# SCH_RTC_SYS_2022-07-16.net
KiCad netlist of a schematic drawn in EasyEDA
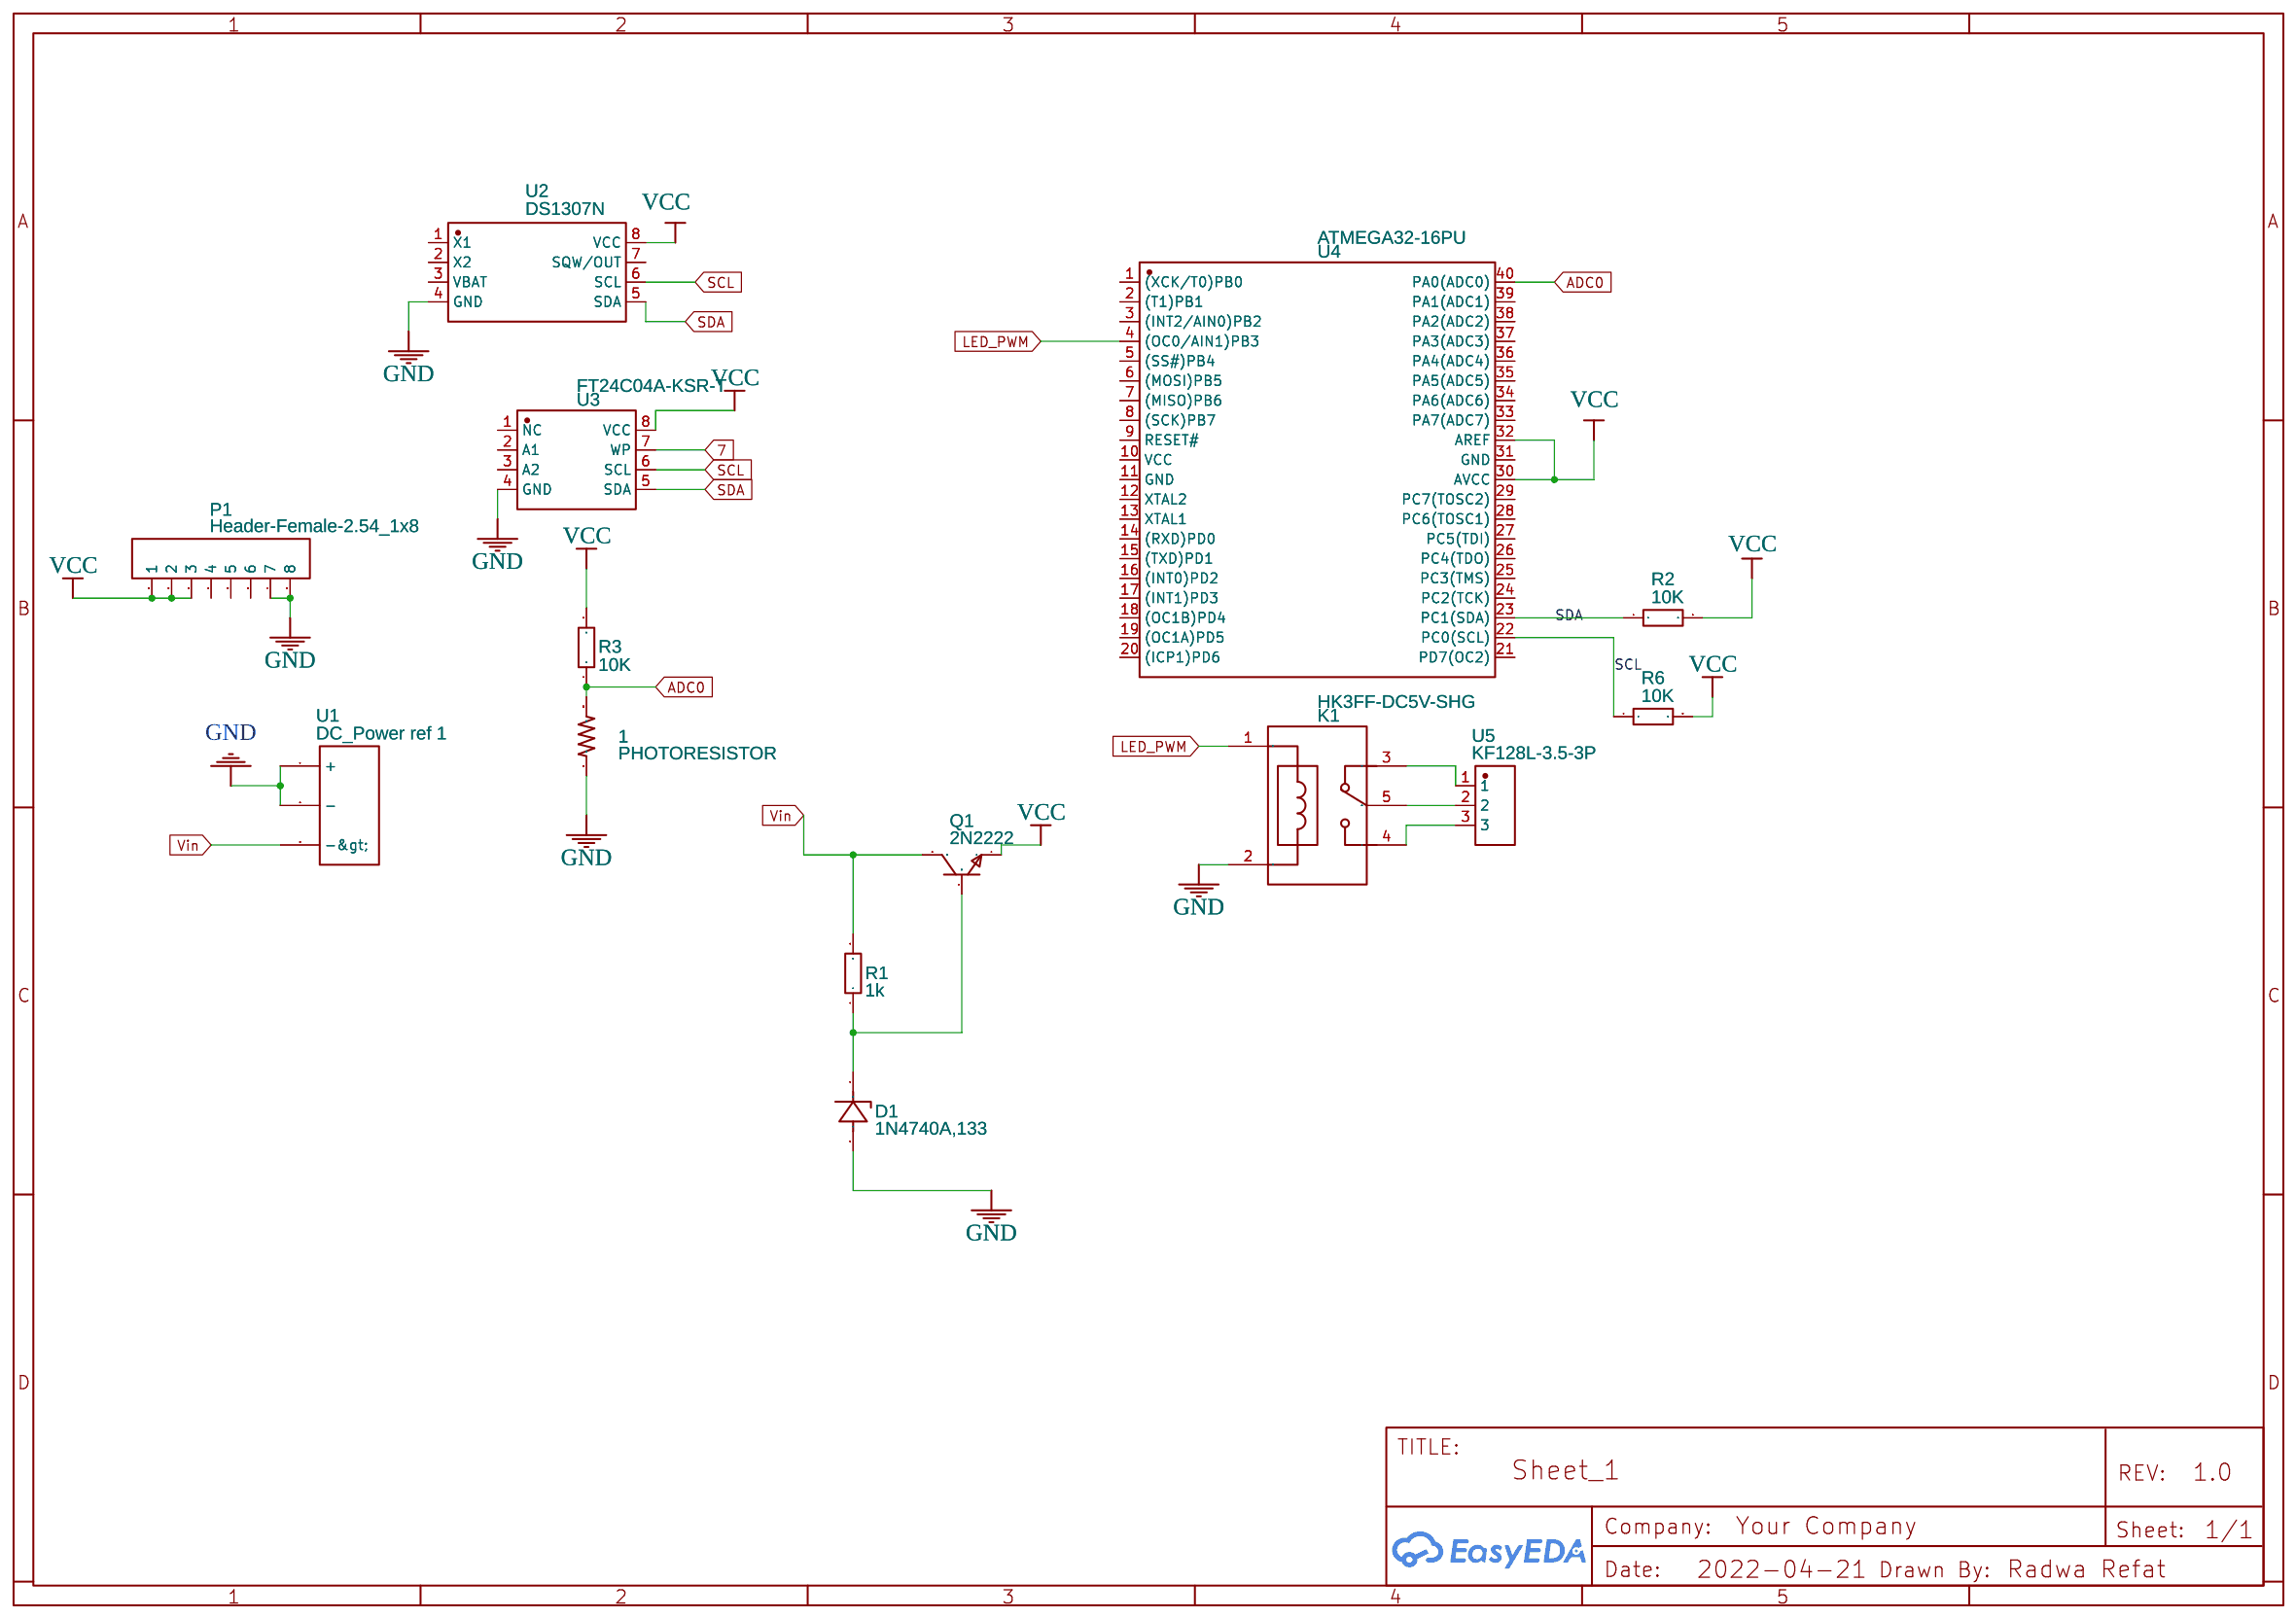
[diagram p0: schematic sheet]

(export (version "E")
  (design (tool "Eeschema 10.0.6"))
  (components
    (comp (ref "1") (value "PHOTORESISTOR") (libsource (lib "") (part "PHOTORESISTOR")))
    (comp (ref "D1")
      (value "1N4740A,133")
      (fields (field (name "BOM_Supplier Part") "C551363"))
      (libsource (lib "") (part "1N4740A,133"))
    )
    (comp (ref "K1")
      (value "HK3FF-DC5V-SHG")
      (fields (field (name "BOM_Supplier Part") "C27840"))
      (libsource (lib "") (part "HK3FF-DC5V-SHG"))
    )
    (comp (ref "P1")
      (value "Header-Female-2.54_1x8")
      (fields
        (field (name "BOM_Manufacturer Part") "Female headerHDR1X8-2.54")
        (field (name "BOM_Supplier Part") "C27438")
      )
      (libsource (lib "") (part "Header-Female-2.54_1x8"))
    )
    (comp (ref "Q1")
      (value "2N2222")
      (fields (field (name "BOM_Supplier Part") "C118536"))
      (libsource (lib "") (part "2N2222"))
    )
    (comp (ref "R1")
      (value "1k")
      (fields (field (name "BOM_Supplier Part") "C337046"))
      (libsource (lib "") (part "MF1/4WS ±1% 10K OTB5"))
    )
    (comp (ref "R2")
      (value "10K")
      (fields (field (name "BOM_Supplier Part") "C337046"))
      (libsource (lib "") (part "MF1/4WS ±1% 10K OTB5_1"))
    )
    (comp (ref "R3")
      (value "10K")
      (fields (field (name "BOM_Supplier Part") "C337046"))
      (libsource (lib "") (part "MF1/4WS ±1% 10K OTB5"))
    )
    (comp (ref "R6")
      (value "10K")
      (fields (field (name "BOM_Supplier Part") "C337046"))
      (libsource (lib "") (part "MF1/4WS ±1% 10K OTB5_1"))
    )
    (comp (ref "U1")
      (value "DC_Power ref 1")
      (fields (field (name "Manufacturer") "Kobiconn") (field (name "BOM_Manufacturer Part") "163-179PH-EX"))
      (libsource (lib "") (part "DC_Power ref 1"))
    )
    (comp (ref "U2")
      (value "DS1307N")
      (fields (field (name "BOM_Supplier Part") "C434596"))
      (libsource (lib "") (part "DS1307N"))
    )
    (comp (ref "U3")
      (value "FT24C04A-KSR-T")
      (fields (field (name "BOM_Supplier Part") "C232866"))
      (libsource (lib "") (part "FT24C04A-KSR-T"))
    )
    (comp (ref "U4")
      (value "ATMEGA32-16PU")
      (fields (field (name "BOM_Supplier Part") "C1337273"))
      (libsource (lib "") (part "ATMEGA32-16PU"))
    )
    (comp (ref "U5")
      (value "KF128L-3.5-3P")
      (fields (field (name "BOM_Supplier Part") "C474931"))
      (libsource (lib "") (part "KF128L-3.5-3P"))
    )
  )
  (nets
    (net (code "1") (name "7") (class "Default")
      (node (ref "U3") (pin "7") (pinfunction "WP_7") (pintype "unspecified"))
    )
    (net (code "2") (name "ADC0") (class "Default")
      (node (ref "1") (pin "P$2") (pinfunction "2_P$2") (pintype "bidirectional"))
      (node (ref "R3") (pin "1") (pinfunction "1_1") (pintype "input"))
      (node (ref "U4") (pin "40") (pinfunction "PA0(ADC0)_40") (pintype "unspecified"))
    )
    (net (code "3") (name "GND") (class "Default")
      (node (ref "1") (pin "P$1") (pinfunction "1_P$1") (pintype "bidirectional"))
      (node (ref "D1") (pin "2") (pinfunction "A_2") (pintype "unspecified"))
      (node (ref "K1") (pin "2") (pinfunction "2_2") (pintype "unspecified"))
      (node (ref "P1") (pin "7") (pinfunction "7_7") (pintype "input"))
      (node (ref "P1") (pin "8") (pinfunction "8_8") (pintype "input"))
      (node (ref "U1") (pin "1") (pinfunction "+_1") (pintype "unspecified"))
      (node (ref "U1") (pin "2") (pinfunction "-_2") (pintype "unspecified"))
      (node (ref "U2") (pin "4") (pinfunction "GND_4") (pintype "unspecified"))
      (node (ref "U3") (pin "4") (pinfunction "GND_4") (pintype "unspecified"))
    )
    (net (code "4") (name "LED_PWM") (class "Default")
      (node (ref "K1") (pin "1") (pinfunction "1_1") (pintype "unspecified"))
      (node (ref "U4") (pin "4") (pinfunction "(OC0/AIN1)PB3_4") (pintype "unspecified"))
    )
    (net (code "5") (name "Net-(D1-K)") (class "Default")
      (node (ref "D1") (pin "1") (pinfunction "K_1") (pintype "unspecified"))
      (node (ref "Q1") (pin "2") (pinfunction "B_2") (pintype "unspecified"))
      (node (ref "R1") (pin "1") (pinfunction "1_1") (pintype "input"))
    )
    (net (code "6") (name "Net-(K1-Pad3)") (class "Default")
      (node (ref "K1") (pin "3") (pinfunction "3_3") (pintype "unspecified"))
      (node (ref "U5") (pin "1") (pinfunction "1_1") (pintype "unspecified"))
    )
    (net (code "7") (name "Net-(K1-Pad4)") (class "Default")
      (node (ref "K1") (pin "4") (pinfunction "4_4") (pintype "unspecified"))
      (node (ref "U5") (pin "3") (pinfunction "3_3") (pintype "unspecified"))
    )
    (net (code "8") (name "Net-(K1-Pad5)") (class "Default")
      (node (ref "K1") (pin "5") (pinfunction "5_5") (pintype "unspecified"))
      (node (ref "U5") (pin "2") (pinfunction "2_2") (pintype "unspecified"))
    )
    (net (code "9") (name "SCL") (class "Default")
      (node (ref "R6") (pin "1") (pinfunction "1_1") (pintype "input"))
      (node (ref "U2") (pin "6") (pinfunction "SCL_6") (pintype "unspecified"))
      (node (ref "U3") (pin "6") (pinfunction "SCL_6") (pintype "unspecified"))
      (node (ref "U4") (pin "22") (pinfunction "PC0(SCL)_22") (pintype "unspecified"))
    )
    (net (code "10") (name "SDA") (class "Default")
      (node (ref "R2") (pin "1") (pinfunction "1_1") (pintype "input"))
      (node (ref "U2") (pin "5") (pinfunction "SDA_5") (pintype "unspecified"))
      (node (ref "U3") (pin "5") (pinfunction "SDA_5") (pintype "unspecified"))
      (node (ref "U4") (pin "23") (pinfunction "PC1(SDA)_23") (pintype "unspecified"))
    )
    (net (code "11") (name "VCC") (class "Default")
      (node (ref "P1") (pin "1") (pinfunction "1_1") (pintype "input"))
      (node (ref "P1") (pin "2") (pinfunction "2_2") (pintype "input"))
      (node (ref "P1") (pin "3") (pinfunction "3_3") (pintype "input"))
      (node (ref "Q1") (pin "1") (pinfunction "E_1") (pintype "unspecified"))
      (node (ref "R2") (pin "2") (pinfunction "2_2") (pintype "input"))
      (node (ref "R3") (pin "2") (pinfunction "2_2") (pintype "input"))
      (node (ref "R6") (pin "2") (pinfunction "2_2") (pintype "input"))
      (node (ref "U2") (pin "8") (pinfunction "VCC_8") (pintype "unspecified"))
      (node (ref "U3") (pin "8") (pinfunction "VCC_8") (pintype "unspecified"))
      (node (ref "U4") (pin "30") (pinfunction "AVCC_30") (pintype "unspecified"))
      (node (ref "U4") (pin "32") (pinfunction "AREF_32") (pintype "unspecified"))
    )
    (net (code "12") (name "Vin") (class "Default")
      (node (ref "Q1") (pin "3") (pinfunction "C_3") (pintype "unspecified"))
      (node (ref "R1") (pin "2") (pinfunction "2_2") (pintype "input"))
      (node (ref "U1") (pin "3") (pinfunction "-&gt;_3") (pintype "unspecified"))
    )
    (net (code "13") (name "unconnected-(P1-Pad4)") (class "Default")
      (node (ref "P1") (pin "4") (pinfunction "4_4") (pintype "input"))
    )
    (net (code "14") (name "unconnected-(P1-Pad5)") (class "Default")
      (node (ref "P1") (pin "5") (pinfunction "5_5") (pintype "input"))
    )
    (net (code "15") (name "unconnected-(P1-Pad6)") (class "Default")
      (node (ref "P1") (pin "6") (pinfunction "6_6") (pintype "input"))
    )
    (net (code "16") (name "unconnected-(U2-SQW{slash}OUT-Pad7)") (class "Default")
      (node (ref "U2") (pin "7") (pinfunction "SQW/OUT_7") (pintype "unspecified"))
    )
    (net (code "17") (name "unconnected-(U2-VBAT-Pad3)") (class "Default")
      (node (ref "U2") (pin "3") (pinfunction "VBAT_3") (pintype "unspecified"))
    )
    (net (code "18") (name "unconnected-(U2-X1-Pad1)") (class "Default")
      (node (ref "U2") (pin "1") (pinfunction "X1_1") (pintype "unspecified"))
    )
    (net (code "19") (name "unconnected-(U2-X2-Pad2)") (class "Default")
      (node (ref "U2") (pin "2") (pinfunction "X2_2") (pintype "unspecified"))
    )
    (net (code "20") (name "unconnected-(U3-A1-Pad2)") (class "Default")
      (node (ref "U3") (pin "2") (pinfunction "A1_2") (pintype "unspecified"))
    )
    (net (code "21") (name "unconnected-(U3-A2-Pad3)") (class "Default")
      (node (ref "U3") (pin "3") (pinfunction "A2_3") (pintype "unspecified"))
    )
    (net (code "22") (name "unconnected-(U3-NC-Pad1)") (class "Default")
      (node (ref "U3") (pin "1") (pinfunction "NC_1") (pintype "unspecified"))
    )
    (net (code "23") (name "unconnected-(U4-(ICP1)PD6-Pad20)") (class "Default")
      (node (ref "U4") (pin "20") (pinfunction "(ICP1)PD6_20") (pintype "unspecified"))
    )
    (net (code "24") (name "unconnected-(U4-(INT0)PD2-Pad16)") (class "Default")
      (node (ref "U4") (pin "16") (pinfunction "(INT0)PD2_16") (pintype "unspecified"))
    )
    (net (code "25") (name "unconnected-(U4-(INT1)PD3-Pad17)") (class "Default")
      (node (ref "U4") (pin "17") (pinfunction "(INT1)PD3_17") (pintype "unspecified"))
    )
    (net (code "26") (name "unconnected-(U4-(INT2{slash}AIN0)PB2-Pad3)") (class "Default")
      (node (ref "U4") (pin "3") (pinfunction "(INT2/AIN0)PB2_3") (pintype "unspecified"))
    )
    (net (code "27") (name "unconnected-(U4-(MISO)PB6-Pad7)") (class "Default")
      (node (ref "U4") (pin "7") (pinfunction "(MISO)PB6_7") (pintype "unspecified"))
    )
    (net (code "28") (name "unconnected-(U4-(MOSI)PB5-Pad6)") (class "Default")
      (node (ref "U4") (pin "6") (pinfunction "(MOSI)PB5_6") (pintype "unspecified"))
    )
    (net (code "29") (name "unconnected-(U4-(OC1A)PD5-Pad19)") (class "Default")
      (node (ref "U4") (pin "19") (pinfunction "(OC1A)PD5_19") (pintype "unspecified"))
    )
    (net (code "30") (name "unconnected-(U4-(OC1B)PD4-Pad18)") (class "Default")
      (node (ref "U4") (pin "18") (pinfunction "(OC1B)PD4_18") (pintype "unspecified"))
    )
    (net (code "31") (name "unconnected-(U4-(RXD)PD0-Pad14)") (class "Default")
      (node (ref "U4") (pin "14") (pinfunction "(RXD)PD0_14") (pintype "unspecified"))
    )
    (net (code "32") (name "unconnected-(U4-(SCK)PB7-Pad8)") (class "Default")
      (node (ref "U4") (pin "8") (pinfunction "(SCK)PB7_8") (pintype "unspecified"))
    )
    (net (code "33") (name "unconnected-(U4-(SS#)PB4-Pad5)") (class "Default")
      (node (ref "U4") (pin "5") (pinfunction "(SS#)PB4_5") (pintype "unspecified"))
    )
    (net (code "34") (name "unconnected-(U4-(T1)PB1-Pad2)") (class "Default")
      (node (ref "U4") (pin "2") (pinfunction "(T1)PB1_2") (pintype "unspecified"))
    )
    (net (code "35") (name "unconnected-(U4-(TXD)PD1-Pad15)") (class "Default")
      (node (ref "U4") (pin "15") (pinfunction "(TXD)PD1_15") (pintype "unspecified"))
    )
    (net (code "36") (name "unconnected-(U4-(XCK{slash}T0)PB0-Pad1)") (class "Default")
      (node (ref "U4") (pin "1") (pinfunction "(XCK/T0)PB0_1") (pintype "unspecified"))
    )
    (net (code "37") (name "unconnected-(U4-GND-Pad11)") (class "Default")
      (node (ref "U4") (pin "11") (pinfunction "GND_11") (pintype "unspecified"))
    )
    (net (code "38") (name "unconnected-(U4-GND-Pad31)") (class "Default")
      (node (ref "U4") (pin "31") (pinfunction "GND_31") (pintype "unspecified"))
    )
    (net (code "39") (name "unconnected-(U4-PA1(ADC1)-Pad39)") (class "Default")
      (node (ref "U4") (pin "39") (pinfunction "PA1(ADC1)_39") (pintype "unspecified"))
    )
    (net (code "40") (name "unconnected-(U4-PA2(ADC2)-Pad38)") (class "Default")
      (node (ref "U4") (pin "38") (pinfunction "PA2(ADC2)_38") (pintype "unspecified"))
    )
    (net (code "41") (name "unconnected-(U4-PA3(ADC3)-Pad37)") (class "Default")
      (node (ref "U4") (pin "37") (pinfunction "PA3(ADC3)_37") (pintype "unspecified"))
    )
    (net (code "42") (name "unconnected-(U4-PA4(ADC4)-Pad36)") (class "Default")
      (node (ref "U4") (pin "36") (pinfunction "PA4(ADC4)_36") (pintype "unspecified"))
    )
    (net (code "43") (name "unconnected-(U4-PA5(ADC5)-Pad35)") (class "Default")
      (node (ref "U4") (pin "35") (pinfunction "PA5(ADC5)_35") (pintype "unspecified"))
    )
    (net (code "44") (name "unconnected-(U4-PA6(ADC6)-Pad34)") (class "Default")
      (node (ref "U4") (pin "34") (pinfunction "PA6(ADC6)_34") (pintype "unspecified"))
    )
    (net (code "45") (name "unconnected-(U4-PA7(ADC7)-Pad33)") (class "Default")
      (node (ref "U4") (pin "33") (pinfunction "PA7(ADC7)_33") (pintype "unspecified"))
    )
    (net (code "46") (name "unconnected-(U4-PC2(TCK)-Pad24)") (class "Default")
      (node (ref "U4") (pin "24") (pinfunction "PC2(TCK)_24") (pintype "unspecified"))
    )
    (net (code "47") (name "unconnected-(U4-PC3(TMS)-Pad25)") (class "Default")
      (node (ref "U4") (pin "25") (pinfunction "PC3(TMS)_25") (pintype "unspecified"))
    )
    (net (code "48") (name "unconnected-(U4-PC4(TDO)-Pad26)") (class "Default")
      (node (ref "U4") (pin "26") (pinfunction "PC4(TDO)_26") (pintype "unspecified"))
    )
    (net (code "49") (name "unconnected-(U4-PC5(TDI)-Pad27)") (class "Default")
      (node (ref "U4") (pin "27") (pinfunction "PC5(TDI)_27") (pintype "unspecified"))
    )
    (net (code "50") (name "unconnected-(U4-PC6(TOSC1)-Pad28)") (class "Default")
      (node (ref "U4") (pin "28") (pinfunction "PC6(TOSC1)_28") (pintype "unspecified"))
    )
    (net (code "51") (name "unconnected-(U4-PC7(TOSC2)-Pad29)") (class "Default")
      (node (ref "U4") (pin "29") (pinfunction "PC7(TOSC2)_29") (pintype "unspecified"))
    )
    (net (code "52") (name "unconnected-(U4-PD7(OC2)-Pad21)") (class "Default")
      (node (ref "U4") (pin "21") (pinfunction "PD7(OC2)_21") (pintype "unspecified"))
    )
    (net (code "53") (name "unconnected-(U4-RESET#-Pad9)") (class "Default")
      (node (ref "U4") (pin "9") (pinfunction "RESET#_9") (pintype "unspecified"))
    )
    (net (code "54") (name "unconnected-(U4-VCC-Pad10)") (class "Default")
      (node (ref "U4") (pin "10") (pinfunction "VCC_10") (pintype "unspecified"))
    )
    (net (code "55") (name "unconnected-(U4-XTAL1-Pad13)") (class "Default")
      (node (ref "U4") (pin "13") (pinfunction "XTAL1_13") (pintype "unspecified"))
    )
    (net (code "56") (name "unconnected-(U4-XTAL2-Pad12)") (class "Default")
      (node (ref "U4") (pin "12") (pinfunction "XTAL2_12") (pintype "unspecified"))
    )
  )
)
